# EPBooster.net
KiCad netlist of a schematic drawn in EAGLE
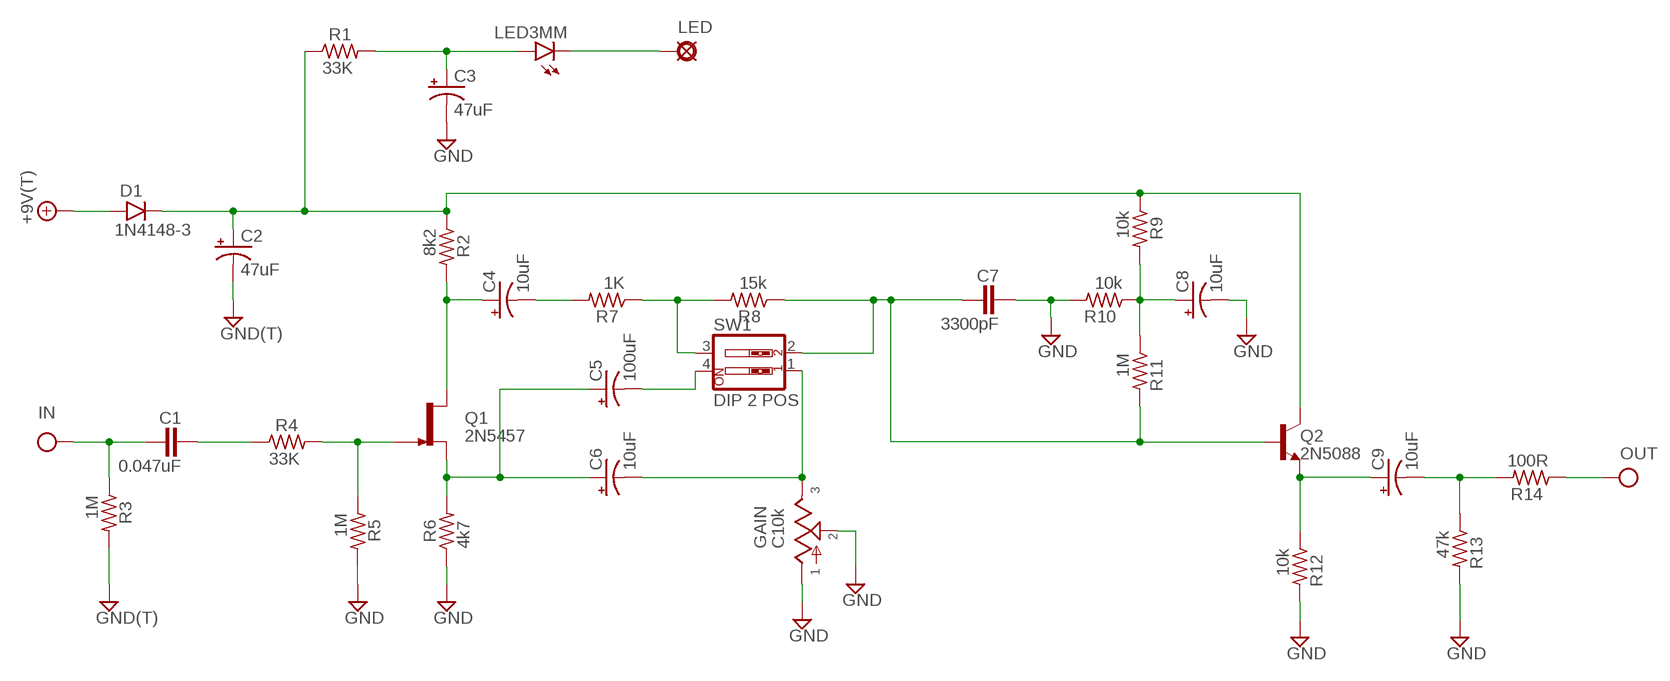
[diagram p0: schematic, sheet 1]

(export (version "E")
  (design (tool "Eeschema 10.0.6"))
  (components
    (comp (ref "+9/18V")
      (value "+9V(T)")
      (footprint "eagle-import:SQUARE")
      (libsource (lib "eagle-import") (part "+9V(T)"))
    )
    (comp (ref "C1")
      (value "0.047uF")
      (footprint "eagle-import:072X025")
      (libsource (lib "eagle-import") (part "072X0252"))
    )
    (comp (ref "C2")
      (value "47uF")
      (footprint "eagle-import:050_020_1")
      (libsource (lib "eagle-import") (part "0501"))
    )
    (comp (ref "C3")
      (value "47uF")
      (footprint "eagle-import:050_020_1")
      (libsource (lib "eagle-import") (part "0501"))
    )
    (comp (ref "C4")
      (value "10uF")
      (footprint "eagle-import:050_020_1")
      (libsource (lib "eagle-import") (part "0501"))
    )
    (comp (ref "C5")
      (value "100uF")
      (footprint "eagle-import:063_025")
      (libsource (lib "eagle-import") (part "0631"))
    )
    (comp (ref "C6")
      (value "10uF")
      (footprint "eagle-import:050_020_1")
      (libsource (lib "eagle-import") (part "0501"))
    )
    (comp (ref "C7")
      (value "3300pF")
      (footprint "eagle-import:072X025")
      (libsource (lib "eagle-import") (part "072X0252"))
    )
    (comp (ref "C8")
      (value "10uF")
      (footprint "eagle-import:050_020_1")
      (libsource (lib "eagle-import") (part "0501"))
    )
    (comp (ref "C9")
      (value "10uF")
      (footprint "eagle-import:050_020_1")
      (libsource (lib "eagle-import") (part "0501"))
    )
    (comp (ref "D1")
      (value "1N4148-3")
      (footprint "eagle-import:DO35-3")
      (libsource (lib "eagle-import") (part "1N4148-3"))
    )
    (comp (ref "G")
      (value "GND(T)")
      (footprint "eagle-import:SQUARE")
      (libsource (lib "eagle-import") (part "GND(T)"))
    )
    (comp (ref "GAIN")
      (value "C10k")
      (footprint "eagle-import:POT")
      (libsource (lib "eagle-import") (part "POT"))
    )
    (comp (ref "GND")
      (value "GND(T)")
      (footprint "eagle-import:SQUARE")
      (libsource (lib "eagle-import") (part "GND(T)"))
    )
    (comp (ref "IN")
      (value "IN(T)")
      (footprint "eagle-import:SQUARE")
      (libsource (lib "eagle-import") (part "IN(T)"))
    )
    (comp (ref "LED")
      (value "PAD")
      (footprint "eagle-import:SQUARE")
      (libsource (lib "eagle-import") (part "PAD"))
    )
    (comp (ref "LED3MM")
      (value "3MM")
      (footprint "eagle-import:LED3MM")
      (libsource (lib "eagle-import") (part "LED3MM"))
    )
    (comp (ref "OUT")
      (value "OUT(T)")
      (footprint "eagle-import:SQUARE")
      (libsource (lib "eagle-import") (part "OUT(T)"))
    )
    (comp (ref "Q1")
      (value "2N5457")
      (footprint "eagle-import:TO92-")
      (libsource (lib "eagle-import") (part "2N5457"))
    )
    (comp (ref "Q2")
      (value "2N5088")
      (footprint "eagle-import:TO92-")
      (libsource (lib "eagle-import") (part "2N5088"))
    )
    (comp (ref "R1")
      (value "33K")
      (footprint "eagle-import:R0204_2")
      (libsource (lib "eagle-import") (part "3MM.2"))
    )
    (comp (ref "R2")
      (value "8k2")
      (footprint "eagle-import:R0204_2")
      (libsource (lib "eagle-import") (part "3MM.2"))
    )
    (comp (ref "R3")
      (value "1M")
      (footprint "eagle-import:R0204_2")
      (libsource (lib "eagle-import") (part "3MM.2"))
    )
    (comp (ref "R4")
      (value "33K")
      (footprint "eagle-import:R0204_2")
      (libsource (lib "eagle-import") (part "3MM.2"))
    )
    (comp (ref "R5")
      (value "1M")
      (footprint "eagle-import:R0204_2")
      (libsource (lib "eagle-import") (part "3MM.2"))
    )
    (comp (ref "R6")
      (value "4k7")
      (footprint "eagle-import:R0204_2")
      (libsource (lib "eagle-import") (part "3MM.2"))
    )
    (comp (ref "R7")
      (value "1K")
      (footprint "eagle-import:R0204_2")
      (libsource (lib "eagle-import") (part "3MM.2"))
    )
    (comp (ref "R8")
      (value "15k")
      (footprint "eagle-import:R0204_2")
      (libsource (lib "eagle-import") (part "3MM.2"))
    )
    (comp (ref "R9")
      (value "10k")
      (footprint "eagle-import:R0204_2")
      (libsource (lib "eagle-import") (part "3MM.2"))
    )
    (comp (ref "R10")
      (value "10k")
      (footprint "eagle-import:R0204_2")
      (libsource (lib "eagle-import") (part "3MM.2"))
    )
    (comp (ref "R11")
      (value "1M")
      (footprint "eagle-import:R0204_2")
      (libsource (lib "eagle-import") (part "3MM.2"))
    )
    (comp (ref "R12")
      (value "10k")
      (footprint "eagle-import:R0204_2")
      (libsource (lib "eagle-import") (part "3MM.2"))
    )
    (comp (ref "R13")
      (value "47k")
      (footprint "eagle-import:R0204_2")
      (libsource (lib "eagle-import") (part "3MM.2"))
    )
    (comp (ref "R14")
      (value "100R")
      (footprint "eagle-import:R0204_2")
      (libsource (lib "eagle-import") (part "3MM.2"))
    )
    (comp (ref "SW1")
      (value "DIP 2 POS")
      (footprint "eagle-import:EDG-02")
      (libsource (lib "eagle-import") (part "SW_DIP-2"))
    )
  )
  (nets
    (net (code "1") (name "+9V(T)") (class "Default")
      (node (ref "+9/18V") (pin "1") (pinfunction "+9V_1") (pintype "power_in"))
      (node (ref "D1") (pin "A") (pinfunction "A_A") (pintype "passive"))
    )
    (net (code "2") (name "GND") (class "Default")
      (node (ref "C2") (pin "-") (pinfunction "-_-") (pintype "passive"))
      (node (ref "C3") (pin "-") (pinfunction "-_-") (pintype "passive"))
      (node (ref "C7") (pin "2") (pinfunction "2_2") (pintype "passive"))
      (node (ref "C8") (pin "-") (pinfunction "-_-") (pintype "passive"))
      (node (ref "G") (pin "1") (pinfunction "GND_1") (pintype "power_in"))
      (node (ref "GAIN") (pin "1") (pinfunction "1_1") (pintype "passive"))
      (node (ref "GAIN") (pin "2") (pinfunction "2_2") (pintype "passive"))
      (node (ref "GND") (pin "1") (pinfunction "GND_1") (pintype "power_in"))
      (node (ref "R10") (pin "2") (pinfunction "2_2") (pintype "passive"))
      (node (ref "R12") (pin "2") (pinfunction "2_2") (pintype "passive"))
      (node (ref "R13") (pin "2") (pinfunction "2_2") (pintype "passive"))
      (node (ref "R3") (pin "2") (pinfunction "2_2") (pintype "passive"))
      (node (ref "R5") (pin "2") (pinfunction "2_2") (pintype "passive"))
      (node (ref "R6") (pin "1") (pinfunction "1_1") (pintype "passive"))
    )
    (net (code "3") (name "IN(T)") (class "Default")
      (node (ref "C1") (pin "1") (pinfunction "1_1") (pintype "passive"))
      (node (ref "IN") (pin "1") (pinfunction "IN_1") (pintype "power_in"))
      (node (ref "R3") (pin "1") (pinfunction "1_1") (pintype "passive"))
    )
    (net (code "4") (name "Net-(C1-Pad2)") (class "Default")
      (node (ref "C1") (pin "2") (pinfunction "2_2") (pintype "passive"))
      (node (ref "R4") (pin "1") (pinfunction "1_1") (pintype "passive"))
    )
    (net (code "5") (name "Net-(C3-Pad+)") (class "Default")
      (node (ref "C3") (pin "+") (pinfunction "+_+") (pintype "passive"))
      (node (ref "LED3MM") (pin "A") (pinfunction "A_A") (pintype "passive"))
      (node (ref "R1") (pin "2") (pinfunction "2_2") (pintype "passive"))
    )
    (net (code "6") (name "Net-(C4-Pad-)") (class "Default")
      (node (ref "C4") (pin "-") (pinfunction "-_-") (pintype "passive"))
      (node (ref "R7") (pin "2") (pinfunction "2_2") (pintype "passive"))
    )
    (net (code "7") (name "Net-(C5-Pad-)") (class "Default")
      (node (ref "C5") (pin "-") (pinfunction "-_-") (pintype "passive"))
      (node (ref "SW1") (pin "4") (pinfunction "4_4") (pintype "passive"))
    )
    (net (code "8") (name "Net-(C6-Pad-)") (class "Default")
      (node (ref "C6") (pin "-") (pinfunction "-_-") (pintype "passive"))
      (node (ref "GAIN") (pin "3") (pinfunction "3_3") (pintype "passive"))
      (node (ref "SW1") (pin "1") (pinfunction "1_1") (pintype "passive"))
    )
    (net (code "9") (name "Net-(C8-Pad+)") (class "Default")
      (node (ref "C8") (pin "+") (pinfunction "+_+") (pintype "passive"))
      (node (ref "R10") (pin "1") (pinfunction "1_1") (pintype "passive"))
      (node (ref "R11") (pin "1") (pinfunction "1_1") (pintype "passive"))
      (node (ref "R9") (pin "2") (pinfunction "2_2") (pintype "passive"))
    )
    (net (code "10") (name "Net-(C9-Pad-)") (class "Default")
      (node (ref "C9") (pin "-") (pinfunction "-_-") (pintype "passive"))
      (node (ref "R13") (pin "1") (pinfunction "1_1") (pintype "passive"))
      (node (ref "R14") (pin "2") (pinfunction "2_2") (pintype "passive"))
    )
    (net (code "11") (name "Net-(LED-PAD)") (class "Default")
      (node (ref "LED") (pin "1") (pinfunction "PAD_1") (pintype "passive"))
      (node (ref "LED3MM") (pin "K") (pinfunction "C_K") (pintype "passive"))
    )
    (net (code "12") (name "Net-(Q1-D)") (class "Default")
      (node (ref "C4") (pin "+") (pinfunction "+_+") (pintype "passive"))
      (node (ref "Q1") (pin "3") (pinfunction "D_3") (pintype "passive"))
      (node (ref "R2") (pin "2") (pinfunction "2_2") (pintype "passive"))
    )
    (net (code "13") (name "Net-(Q1-G)") (class "Default")
      (node (ref "Q1") (pin "1") (pinfunction "G_1") (pintype "passive"))
      (node (ref "R4") (pin "2") (pinfunction "2_2") (pintype "passive"))
      (node (ref "R5") (pin "1") (pinfunction "1_1") (pintype "passive"))
    )
    (net (code "14") (name "Net-(Q1-S)") (class "Default")
      (node (ref "C5") (pin "+") (pinfunction "+_+") (pintype "passive"))
      (node (ref "C6") (pin "+") (pinfunction "+_+") (pintype "passive"))
      (node (ref "Q1") (pin "2") (pinfunction "S_2") (pintype "passive"))
      (node (ref "R6") (pin "2") (pinfunction "2_2") (pintype "passive"))
    )
    (net (code "15") (name "Net-(Q2-B)") (class "Default")
      (node (ref "C7") (pin "1") (pinfunction "1_1") (pintype "passive"))
      (node (ref "Q2") (pin "2") (pinfunction "B_2") (pintype "passive"))
      (node (ref "R11") (pin "2") (pinfunction "2_2") (pintype "passive"))
      (node (ref "R8") (pin "1") (pinfunction "1_1") (pintype "passive"))
      (node (ref "SW1") (pin "2") (pinfunction "2_2") (pintype "passive"))
    )
    (net (code "16") (name "Net-(Q2-C)") (class "Default")
      (node (ref "C2") (pin "+") (pinfunction "+_+") (pintype "passive"))
      (node (ref "D1") (pin "C") (pinfunction "C_C") (pintype "passive"))
      (node (ref "Q2") (pin "1") (pinfunction "C_1") (pintype "passive"))
      (node (ref "R1") (pin "1") (pinfunction "1_1") (pintype "passive"))
      (node (ref "R2") (pin "1") (pinfunction "1_1") (pintype "passive"))
      (node (ref "R9") (pin "1") (pinfunction "1_1") (pintype "passive"))
    )
    (net (code "17") (name "Net-(Q2-E)") (class "Default")
      (node (ref "C9") (pin "+") (pinfunction "+_+") (pintype "passive"))
      (node (ref "Q2") (pin "3") (pinfunction "E_3") (pintype "passive"))
      (node (ref "R12") (pin "1") (pinfunction "1_1") (pintype "passive"))
    )
    (net (code "18") (name "Net-(R7-Pad1)") (class "Default")
      (node (ref "R7") (pin "1") (pinfunction "1_1") (pintype "passive"))
      (node (ref "R8") (pin "2") (pinfunction "2_2") (pintype "passive"))
      (node (ref "SW1") (pin "3") (pinfunction "3_3") (pintype "passive"))
    )
    (net (code "19") (name "OUT(T)") (class "Default")
      (node (ref "OUT") (pin "1") (pinfunction "OUT_1") (pintype "power_in"))
      (node (ref "R14") (pin "1") (pinfunction "1_1") (pintype "passive"))
    )
  )
)
